# WiFi_Board_R1_1_0.net
KiCad netlist of a schematic drawn in EAGLE
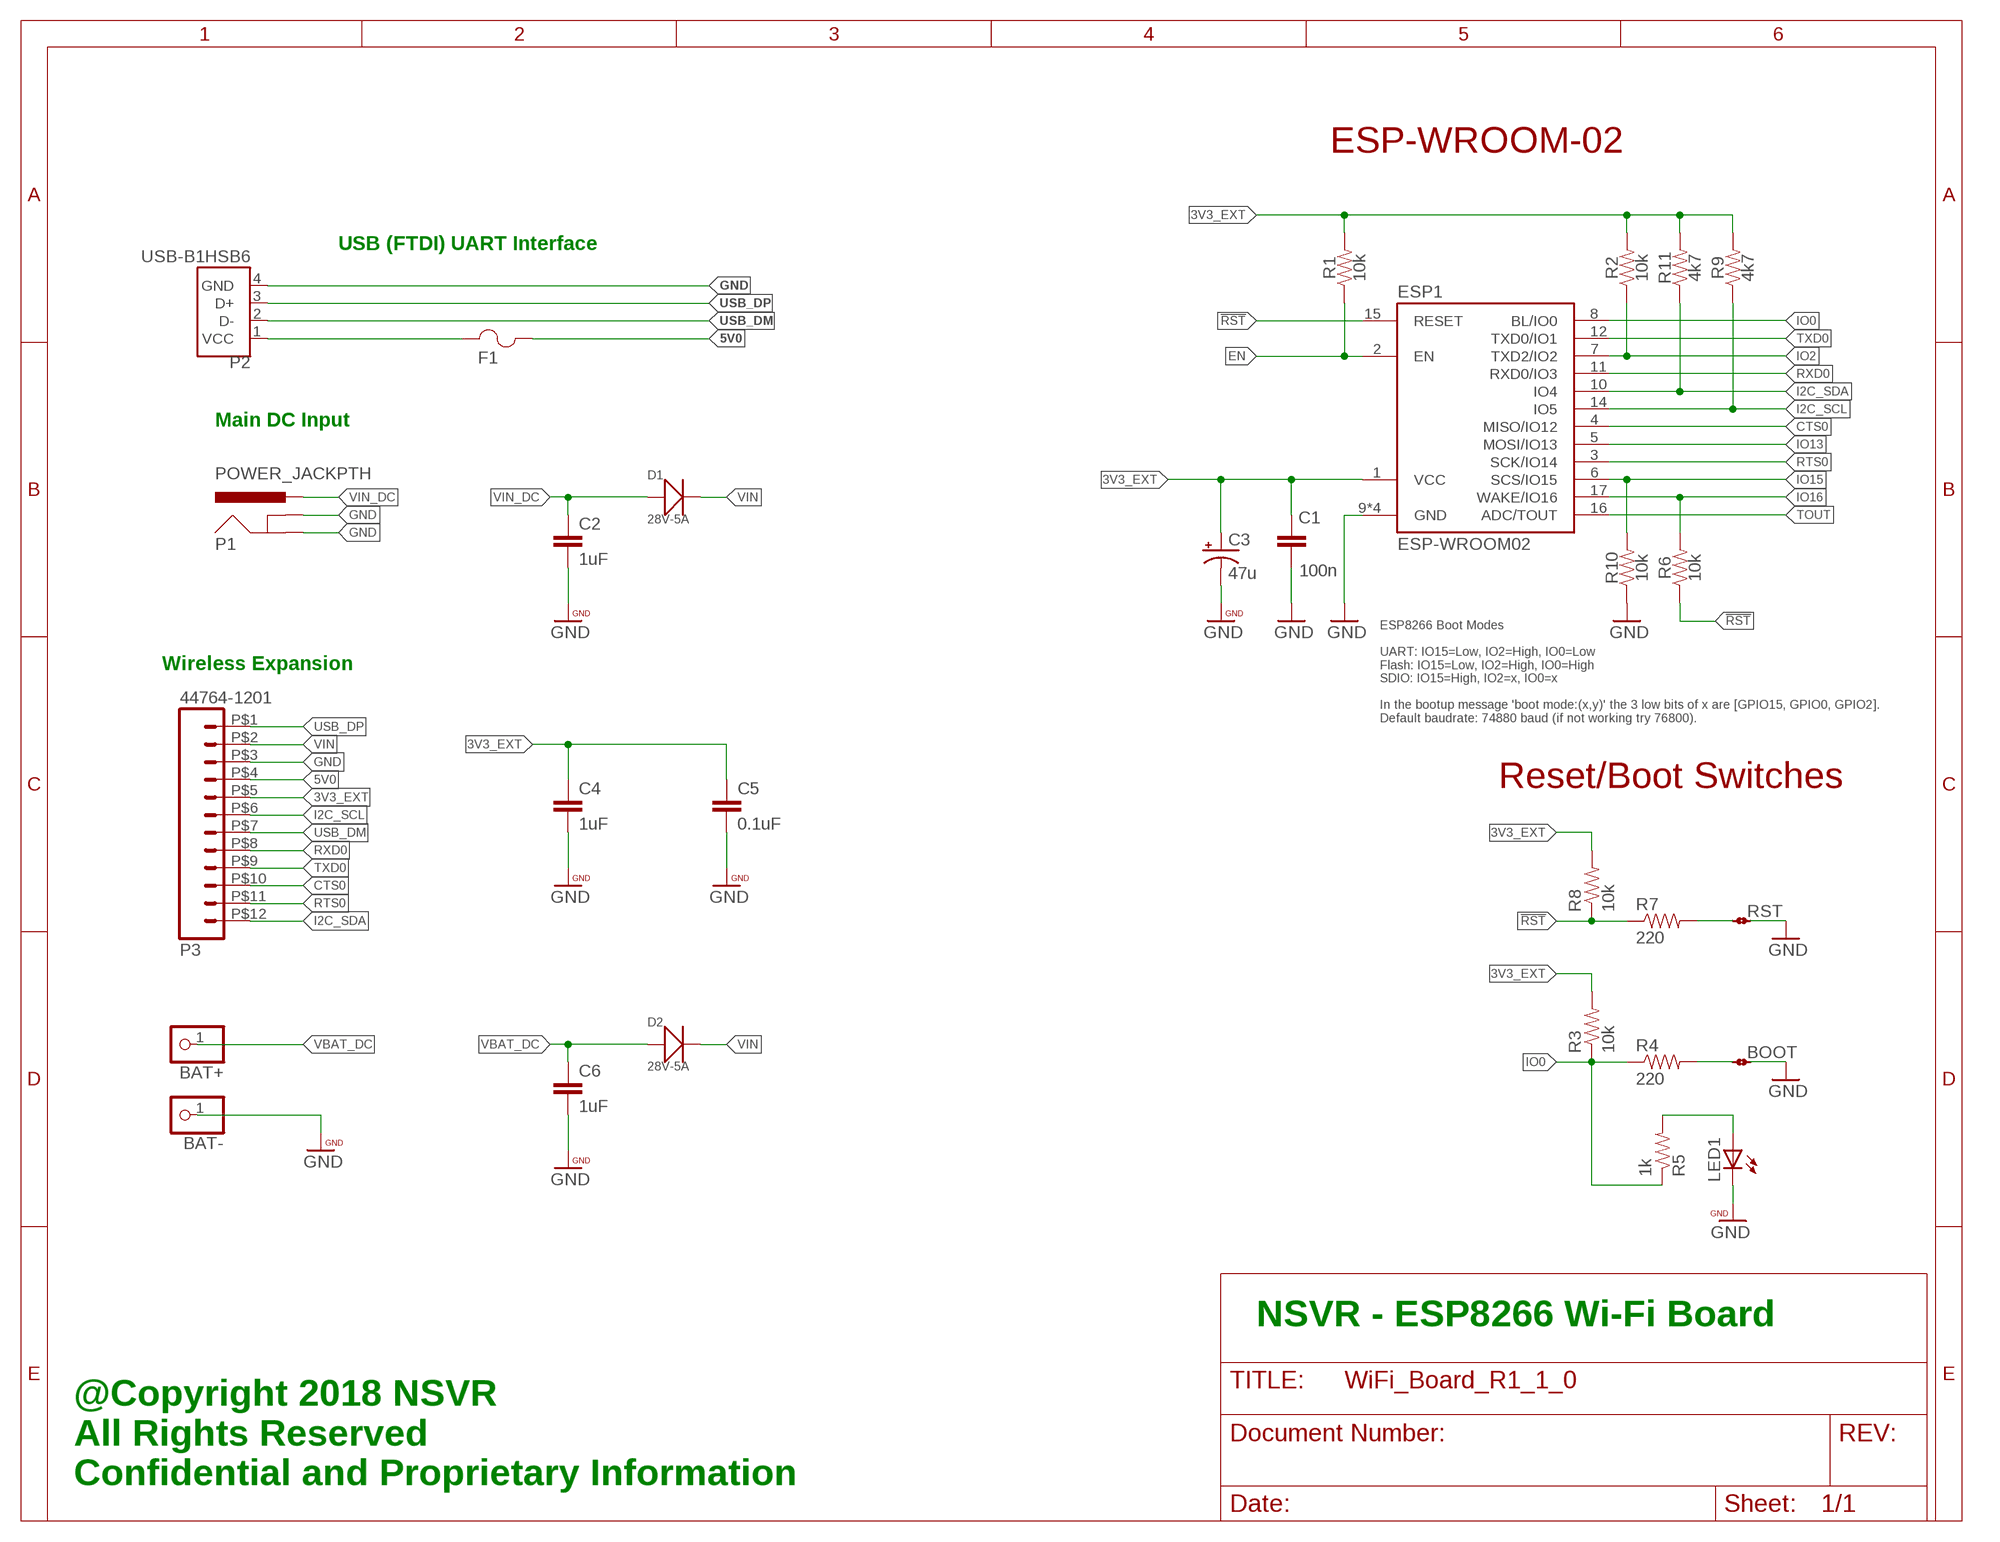
[diagram p0: schematic, sheet 1]

(export (version "E")
  (design (tool "Eeschema 10.0.6"))
  (components
    (comp (ref "BAT+")
      (value "WPAD-1-PTH")
      (footprint "eagle-import:WPAD-1-PTH-2.54")
      (libsource (lib "eagle-import") (part "WPAD-1-PTH"))
    )
    (comp (ref "BAT-")
      (value "WPAD-1-PTH")
      (footprint "eagle-import:WPAD-1-PTH-2.54")
      (libsource (lib "eagle-import") (part "WPAD-1-PTH"))
    )
    (comp (ref "BOOT")
      (value "JMP-2-NO-PTH")
      (footprint "eagle-import:JMP-2-NO-PTH-2.54")
      (libsource (lib "eagle-import") (part "JMP-2-NO-PTH"))
    )
    (comp (ref "C1")
      (value "100n")
      (footprint "eagle-import:0402-CAP")
      (libsource (lib "eagle-import") (part "CAP0402-CAP"))
    )
    (comp (ref "C2")
      (value "1uF")
      (footprint "eagle-import:0402-CAP")
      (libsource (lib "eagle-import") (part "CAP0402-CAP"))
    )
    (comp (ref "C3")
      (value "47u")
      (footprint "eagle-import:PANASONIC_D")
      (libsource (lib "eagle-import") (part "CAP_POLD"))
    )
    (comp (ref "C4")
      (value "1uF")
      (footprint "eagle-import:0402-CAP")
      (libsource (lib "eagle-import") (part "CAP0402-CAP"))
    )
    (comp (ref "C5")
      (value "0.1uF")
      (footprint "eagle-import:0402-CAP")
      (libsource (lib "eagle-import") (part "CAP0402-CAP"))
    )
    (comp (ref "C6")
      (value "1uF")
      (footprint "eagle-import:0402-CAP")
      (libsource (lib "eagle-import") (part "CAP0402-CAP"))
    )
    (comp (ref "D1")
      (value "28V-5A")
      (footprint "eagle-import:DO-214AA")
      (fields (field (name "MPN") "SS54B"))
      (libsource (lib "eagle-import") (part "SMD-DIODE-SCHOTTKY-28V-5A(DO-214AA)"))
    )
    (comp (ref "D2")
      (value "28V-5A")
      (footprint "eagle-import:DO-214AA")
      (fields (field (name "MPN") "SS54B"))
      (libsource (lib "eagle-import") (part "SMD-DIODE-SCHOTTKY-28V-5A(DO-214AA)"))
    )
    (comp (ref "ESP1")
      (value "ESP-WROOM02")
      (footprint "eagle-import:ESP-WROOM02")
      (libsource (lib "eagle-import") (part "ESP-WROOM02"))
    )
    (comp (ref "F1")
      (value "1206L050YR")
      (footprint "eagle-import:1206LSERIES")
      (fields (field (name "COPYRIGHT") "Copyright C 2015 Accelerated Designs. All rights reserved"))
      (libsource (lib "eagle-import") (part "1206L050YR"))
    )
    (comp (ref "LED1")
      (value "LEDCHIP-LED0603")
      (footprint "eagle-import:CHIP-LED0603")
      (libsource (lib "eagle-import") (part "LEDCHIP-LED0603"))
    )
    (comp (ref "P1")
      (value "POWER_JACKPTH")
      (footprint "eagle-import:POWER_JACK_PTH")
      (libsource (lib "eagle-import") (part "POWER_JACKPTH"))
    )
    (comp (ref "P2")
      (value "USB-B1HSB6")
      (footprint "eagle-import:OST_USB-B1HSB6")
      (fields (field (name "MF") "On Shore Technology"))
      (libsource (lib "eagle-import") (part "USB-B1HSB6"))
    )
    (comp (ref "P3")
      (value "44764-1201")
      (footprint "eagle-import:44764-1201")
      (libsource (lib "eagle-import") (part "44764-1201"))
    )
    (comp (ref "R1")
      (value "10k")
      (footprint "eagle-import:EIA-0402")
      (libsource (lib "eagle-import") (part "RESISTOR0402-TYP"))
    )
    (comp (ref "R2")
      (value "10k")
      (footprint "eagle-import:EIA-0402")
      (libsource (lib "eagle-import") (part "RESISTOR0402-TYP"))
    )
    (comp (ref "R3")
      (value "10k")
      (footprint "eagle-import:EIA-0402")
      (libsource (lib "eagle-import") (part "RESISTOR0402-TYP"))
    )
    (comp (ref "R4")
      (value "220")
      (footprint "eagle-import:EIA-0402")
      (libsource (lib "eagle-import") (part "RESISTOR0402-TYP"))
    )
    (comp (ref "R5")
      (value "1k")
      (footprint "eagle-import:EIA-0402")
      (libsource (lib "eagle-import") (part "RESISTOR0402-TYP"))
    )
    (comp (ref "R6")
      (value "10k")
      (footprint "eagle-import:EIA-0402")
      (libsource (lib "eagle-import") (part "RESISTOR0402-TYP"))
    )
    (comp (ref "R7")
      (value "220")
      (footprint "eagle-import:EIA-0402")
      (libsource (lib "eagle-import") (part "RESISTOR0402-TYP"))
    )
    (comp (ref "R8")
      (value "10k")
      (footprint "eagle-import:EIA-0402")
      (libsource (lib "eagle-import") (part "RESISTOR0402-TYP"))
    )
    (comp (ref "R9")
      (value "4k7")
      (footprint "eagle-import:EIA-0402")
      (libsource (lib "eagle-import") (part "RESISTOR0402-TYP"))
    )
    (comp (ref "R10")
      (value "10k")
      (footprint "eagle-import:EIA-0402")
      (libsource (lib "eagle-import") (part "RESISTOR0402-TYP"))
    )
    (comp (ref "R11")
      (value "4k7")
      (footprint "eagle-import:EIA-0402")
      (libsource (lib "eagle-import") (part "RESISTOR0402-TYP"))
    )
    (comp (ref "RST")
      (value "JMP-2-NO-PTH")
      (footprint "eagle-import:JMP-2-NO-PTH-2.54")
      (libsource (lib "eagle-import") (part "JMP-2-NO-PTH"))
    )
  )
  (nets
    (net (code "1") (name "/~{RST}") (class "Default")
      (node (ref "ESP1") (pin "15") (pinfunction "RESET_15") (pintype "bidirectional"))
      (node (ref "R6") (pin "1") (pinfunction "1_1") (pintype "passive"))
      (node (ref "R7") (pin "1") (pinfunction "1_1") (pintype "passive"))
      (node (ref "R8") (pin "1") (pinfunction "1_1") (pintype "passive"))
    )
    (net (code "2") (name "3V3_EXT") (class "Default")
      (node (ref "C1") (pin "2") (pinfunction "2_2") (pintype "passive"))
      (node (ref "C3") (pin "+") (pinfunction "+_+") (pintype "passive"))
      (node (ref "C4") (pin "1") (pinfunction "1_1") (pintype "passive"))
      (node (ref "C5") (pin "1") (pinfunction "1_1") (pintype "passive"))
      (node (ref "ESP1") (pin "1") (pinfunction "VCC_1") (pintype "power_in"))
      (node (ref "P3") (pin "P$5") (pinfunction "5_P$5") (pintype "passive"))
      (node (ref "R1") (pin "2") (pinfunction "2_2") (pintype "passive"))
      (node (ref "R11") (pin "2") (pinfunction "2_2") (pintype "passive"))
      (node (ref "R2") (pin "2") (pinfunction "2_2") (pintype "passive"))
      (node (ref "R3") (pin "2") (pinfunction "2_2") (pintype "passive"))
      (node (ref "R8") (pin "2") (pinfunction "2_2") (pintype "passive"))
      (node (ref "R9") (pin "2") (pinfunction "2_2") (pintype "passive"))
    )
    (net (code "3") (name "5V0") (class "Default")
      (node (ref "F1") (pin "2") (pinfunction "2_2") (pintype "passive"))
      (node (ref "P3") (pin "P$4") (pinfunction "4_P$4") (pintype "passive"))
    )
    (net (code "4") (name "CTS0") (class "Default")
      (node (ref "ESP1") (pin "4") (pinfunction "MISO/IO12_4") (pintype "bidirectional"))
      (node (ref "P3") (pin "P$10") (pinfunction "10_P$10") (pintype "passive"))
    )
    (net (code "5") (name "EN") (class "Default")
      (node (ref "ESP1") (pin "2") (pinfunction "EN_2") (pintype "bidirectional"))
      (node (ref "R1") (pin "1") (pinfunction "1_1") (pintype "passive"))
    )
    (net (code "6") (name "GND") (class "Default")
      (node (ref "BAT-") (pin "1") (pinfunction "1_1") (pintype "passive"))
      (node (ref "BOOT") (pin "2") (pinfunction "2_2") (pintype "passive"))
      (node (ref "C1") (pin "1") (pinfunction "1_1") (pintype "passive"))
      (node (ref "C2") (pin "2") (pinfunction "2_2") (pintype "passive"))
      (node (ref "C3") (pin "-") (pinfunction "-_-") (pintype "passive"))
      (node (ref "C4") (pin "2") (pinfunction "2_2") (pintype "passive"))
      (node (ref "C5") (pin "2") (pinfunction "2_2") (pintype "passive"))
      (node (ref "C6") (pin "2") (pinfunction "2_2") (pintype "passive"))
      (node (ref "ESP1") (pin "13") (pinfunction "GND_13") (pintype "power_in"))
      (node (ref "ESP1") (pin "18") (pinfunction "GND_18") (pintype "power_in"))
      (node (ref "ESP1") (pin "9") (pinfunction "GND_9") (pintype "power_in"))
      (node (ref "ESP1") (pin "TP") (pinfunction "GND_TP") (pintype "power_in"))
      (node (ref "LED1") (pin "C") (pinfunction "C_C") (pintype "passive"))
      (node (ref "P1") (pin "GND") (pinfunction "GND_GND") (pintype "bidirectional"))
      (node (ref "P1") (pin "GNDBREAK") (pinfunction "GNDBREAK_GNDBREAK") (pintype "bidirectional"))
      (node (ref "P2") (pin "4") (pinfunction "GND_4") (pintype "power_in"))
      (node (ref "P3") (pin "P$3") (pinfunction "3_P$3") (pintype "passive"))
      (node (ref "R10") (pin "1") (pinfunction "1_1") (pintype "passive"))
      (node (ref "RST") (pin "2") (pinfunction "2_2") (pintype "passive"))
    )
    (net (code "7") (name "I2C_SCL") (class "Default")
      (node (ref "ESP1") (pin "14") (pinfunction "IO5_14") (pintype "bidirectional"))
      (node (ref "P3") (pin "P$6") (pinfunction "6_P$6") (pintype "passive"))
      (node (ref "R9") (pin "1") (pinfunction "1_1") (pintype "passive"))
    )
    (net (code "8") (name "I2C_SDA") (class "Default")
      (node (ref "ESP1") (pin "10") (pinfunction "IO4_10") (pintype "bidirectional"))
      (node (ref "P3") (pin "P$12") (pinfunction "12_P$12") (pintype "passive"))
      (node (ref "R11") (pin "1") (pinfunction "1_1") (pintype "passive"))
    )
    (net (code "9") (name "IO0") (class "Default")
      (node (ref "ESP1") (pin "8") (pinfunction "BL/IO0_8") (pintype "bidirectional"))
      (node (ref "R3") (pin "1") (pinfunction "1_1") (pintype "passive"))
      (node (ref "R4") (pin "1") (pinfunction "1_1") (pintype "passive"))
      (node (ref "R5") (pin "1") (pinfunction "1_1") (pintype "passive"))
    )
    (net (code "10") (name "IO2") (class "Default")
      (node (ref "ESP1") (pin "7") (pinfunction "TXD2/IO2_7") (pintype "bidirectional"))
      (node (ref "R2") (pin "1") (pinfunction "1_1") (pintype "passive"))
    )
    (net (code "11") (name "IO13") (class "Default")
      (node (ref "ESP1") (pin "5") (pinfunction "MOSI/IO13_5") (pintype "bidirectional"))
    )
    (net (code "12") (name "IO15") (class "Default")
      (node (ref "ESP1") (pin "6") (pinfunction "SCS/IO15_6") (pintype "bidirectional"))
      (node (ref "R10") (pin "2") (pinfunction "2_2") (pintype "passive"))
    )
    (net (code "13") (name "IO16") (class "Default")
      (node (ref "ESP1") (pin "17") (pinfunction "WAKE/IO16_17") (pintype "bidirectional"))
      (node (ref "R6") (pin "2") (pinfunction "2_2") (pintype "passive"))
    )
    (net (code "14") (name "Net-(BOOT-Pad1)") (class "Default")
      (node (ref "BOOT") (pin "1") (pinfunction "1_1") (pintype "passive"))
      (node (ref "R4") (pin "2") (pinfunction "2_2") (pintype "passive"))
    )
    (net (code "15") (name "Net-(LED1-PadA)") (class "Default")
      (node (ref "LED1") (pin "A") (pinfunction "A_A") (pintype "passive"))
      (node (ref "R5") (pin "2") (pinfunction "2_2") (pintype "passive"))
    )
    (net (code "16") (name "Net-(P2-VCC)") (class "Default")
      (node (ref "F1") (pin "1") (pinfunction "1_1") (pintype "passive"))
      (node (ref "P2") (pin "1") (pinfunction "VCC_1") (pintype "power_in"))
    )
    (net (code "17") (name "Net-(R7-Pad2)") (class "Default")
      (node (ref "R7") (pin "2") (pinfunction "2_2") (pintype "passive"))
      (node (ref "RST") (pin "1") (pinfunction "1_1") (pintype "passive"))
    )
    (net (code "18") (name "RTS0") (class "Default")
      (node (ref "ESP1") (pin "3") (pinfunction "SCK/IO14_3") (pintype "bidirectional"))
      (node (ref "P3") (pin "P$11") (pinfunction "11_P$11") (pintype "passive"))
    )
    (net (code "19") (name "RXD0") (class "Default")
      (node (ref "ESP1") (pin "11") (pinfunction "RXD0/IO3_11") (pintype "bidirectional"))
      (node (ref "P3") (pin "P$8") (pinfunction "8_P$8") (pintype "passive"))
    )
    (net (code "20") (name "TOUT") (class "Default")
      (node (ref "ESP1") (pin "16") (pinfunction "ADC/TOUT_16") (pintype "bidirectional"))
    )
    (net (code "21") (name "TXD0") (class "Default")
      (node (ref "ESP1") (pin "12") (pinfunction "TXD0/IO1_12") (pintype "bidirectional"))
      (node (ref "P3") (pin "P$9") (pinfunction "9_P$9") (pintype "passive"))
    )
    (net (code "22") (name "USB_DM") (class "Default")
      (node (ref "P2") (pin "2") (pinfunction "D-_2") (pintype "bidirectional"))
      (node (ref "P3") (pin "P$7") (pinfunction "7_P$7") (pintype "passive"))
    )
    (net (code "23") (name "USB_DP") (class "Default")
      (node (ref "P2") (pin "3") (pinfunction "D+_3") (pintype "bidirectional"))
      (node (ref "P3") (pin "P$1") (pinfunction "1_P$1") (pintype "passive"))
    )
    (net (code "24") (name "VBAT_DC") (class "Default")
      (node (ref "BAT+") (pin "1") (pinfunction "1_1") (pintype "passive"))
      (node (ref "C6") (pin "1") (pinfunction "1_1") (pintype "passive"))
      (node (ref "D2") (pin "+") (pinfunction "+_+") (pintype "passive"))
    )
    (net (code "25") (name "VIN") (class "Default")
      (node (ref "D1") (pin "-") (pinfunction "-_-") (pintype "passive"))
      (node (ref "D2") (pin "-") (pinfunction "-_-") (pintype "passive"))
      (node (ref "P3") (pin "P$2") (pinfunction "2_P$2") (pintype "passive"))
    )
    (net (code "26") (name "VIN_DC") (class "Default")
      (node (ref "C2") (pin "1") (pinfunction "1_1") (pintype "passive"))
      (node (ref "D1") (pin "+") (pinfunction "+_+") (pintype "passive"))
      (node (ref "P1") (pin "PWR") (pinfunction "PWR_PWR") (pintype "bidirectional"))
    )
  )
)
